# Read_Time_sensor_Tho_AMT.net
KiCad netlist of a schematic drawn in Altium Designer
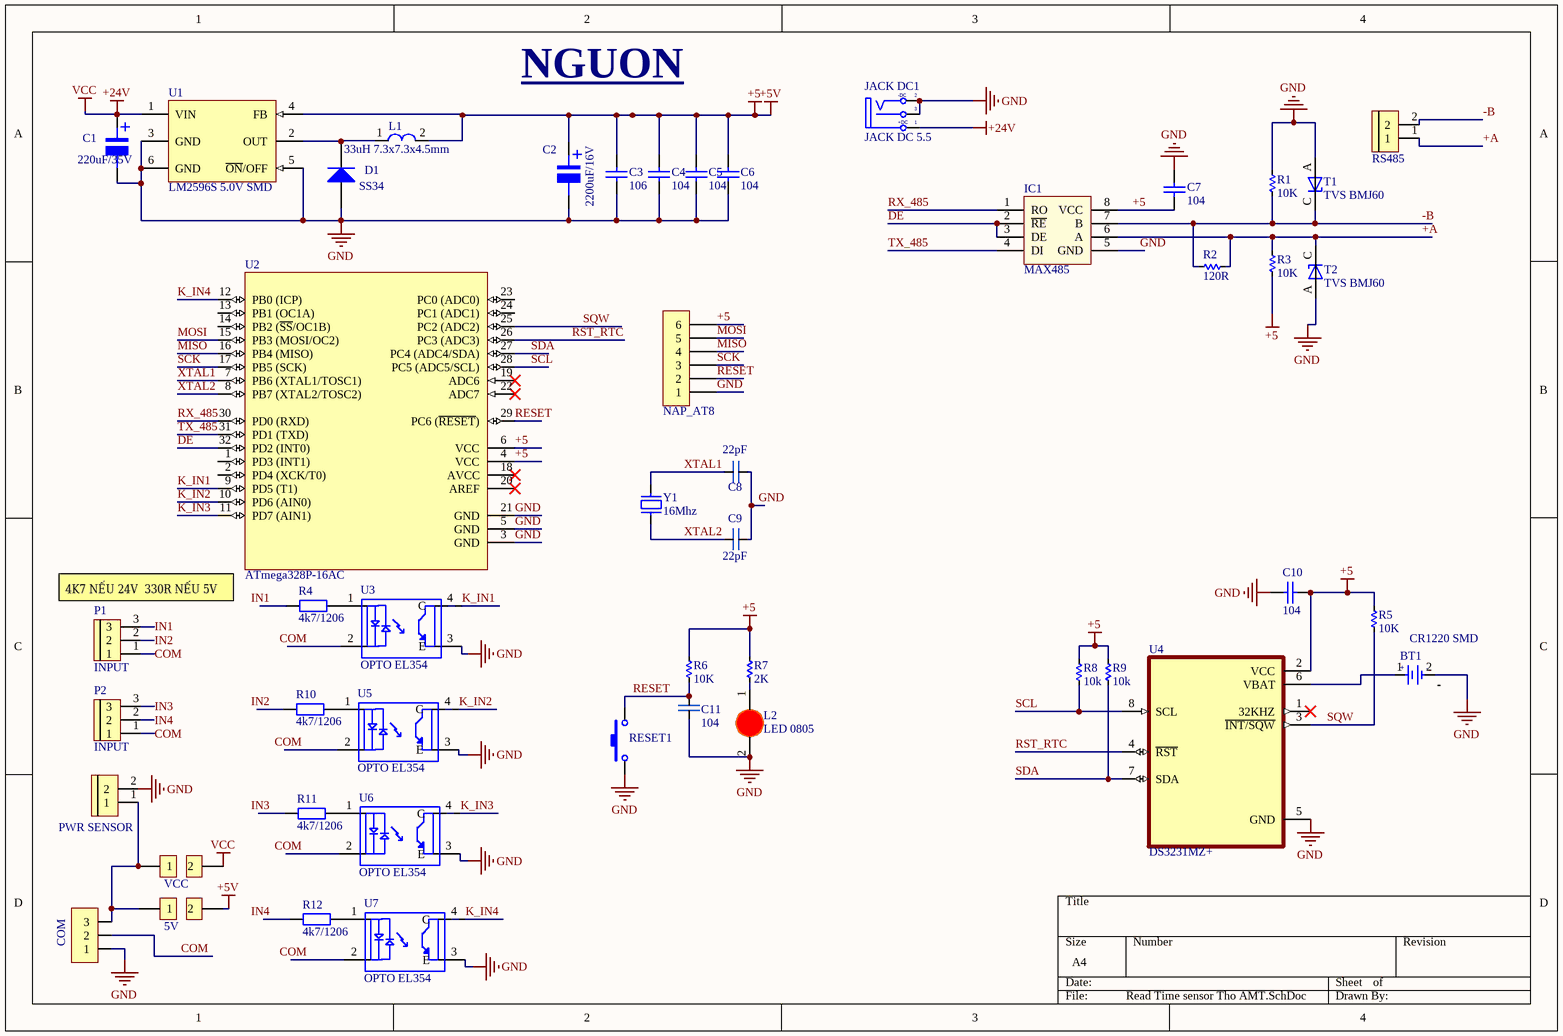
[diagram p0: Read Time sensor Tho AMT.SchDoc]

(export (version "E")
  (design (tool "Eeschema 10.0.6"))
  (components
    (comp (ref "BT1")
      (value "CR1220 SMD")
      (footprint "PIN 2032 DUNG")
      (libsource (lib "NGUYEN VAN ANH HaUI") (part "De pin CR1220 SMD"))
    )
    (comp (ref "C1")
      (value "220uF/35V")
      (footprint "tu nhom 10 (g)")
      (description "Dán 35V")
      (libsource (lib "Altium_Lib_by_KhueNguyenCreator") (part "Tu Nhom 220uF 50V"))
    )
    (comp (ref "C2")
      (value "2200uF/16V")
      (footprint "tu nhom 6.3 (d)")
      (description "Dán")
      (libsource (lib "Altium_Lib_by_KhueNguyenCreator") (part "Tu Nhom 10uF 20V"))
    )
    (comp (ref "C3")
      (value "106")
      (footprint "tu 0805")
      (description "Dán")
      (libsource (lib "Altium_Lib_by_KhueNguyenCreator") (part "Tu 0805 105 50V 10%"))
    )
    (comp (ref "C4")
      (value "104")
      (footprint "tu 0805")
      (description "Dán")
      (libsource (lib "Altium_Lib_by_KhueNguyenCreator") (part "Tu 0805 105 50V 10%"))
    )
    (comp (ref "C5")
      (value "104")
      (footprint "tu 0805")
      (description "Dán")
      (libsource (lib "Altium_Lib_by_KhueNguyenCreator") (part "Tu 0805 105 50V 10%"))
    )
    (comp (ref "C6")
      (value "104")
      (footprint "tu 0805")
      (description "Dán")
      (libsource (lib "Altium_Lib_by_KhueNguyenCreator") (part "Tu 0805 105 50V 10%"))
    )
    (comp (ref "C7")
      (value "104")
      (footprint "TU 0805")
      (description "Dán")
      (libsource (lib "Altium_Lib_by_KhueNguyenCreator") (part "Tu 0805 104 50V 10%"))
    )
    (comp (ref "C8")
      (value "22pF")
      (footprint "TU 0805")
      (libsource (lib "NGUYEN VAN ANH HaUI") (part "TU 0805"))
    )
    (comp (ref "C9")
      (value "22pF")
      (footprint "TU 0805")
      (libsource (lib "NGUYEN VAN ANH HaUI") (part "TU 0805"))
    )
    (comp (ref "C10")
      (value "104")
      (footprint "TU 0805")
      (description "Dán")
      (libsource (lib "Altium_Lib_by_KhueNguyenCreator") (part "Tu 0805 104 50V 10%"))
    )
    (comp (ref "C11")
      (value "104")
      (footprint "TU 0805")
      (libsource (lib "NGUYEN VAN ANH HaUI") (part "TU 0805"))
    )
    (comp (ref "D1")
      (value "SS34")
      (footprint "DIODE SMA")
      (description "Dán")
      (libsource (lib "Altium_Lib_by_KhueNguyenCreator") (part "Diode SS14 ( 1N5819)"))
    )
    (comp (ref "EDG 1")
      (value "RS485")
      (footprint "CON 2 2EDG5.08")
      (description "Cắm")
      (libsource (lib "Altium_Lib_by_KhueNguyenCreator") (part "CON 2 EDG5.08"))
    )
    (comp (ref "EDG 2")
      (value "PWR SENSOR")
      (footprint "CON 2 2EDG5.08")
      (description "Cắm")
      (libsource (lib "Altium_Lib_by_KhueNguyenCreator") (part "CON 2 EDG5.08"))
    )
    (comp (ref "EDG 3")
      (value "COM")
      (footprint "JP 1x3 DT")
      (description "Cắm")
      (libsource (lib "NGUYEN VAN ANH HaUI") (part "JP 1x3 2.54 Duc Thang"))
    )
    (comp (ref "H1")
      (value "NAP_AT8")
      (footprint "Header 6P DC 2.54")
      (description "Cắm")
      (libsource (lib "Altium_Lib_by_KhueNguyenCreator") (part "Header 6P 2.54 Duc Cong"))
    )
    (comp (ref "IC1")
      (value "MAX485")
      (footprint "SO8")
      (description "RS232 - RS485 (Same sn75176)")
      (libsource (lib "Cty1") (part "MAX485"))
    )
    (comp (ref "JACK DC1")
      (value "JACK DC 5.5")
      (footprint "JACK DC 5.5")
      (libsource (lib "NGUYEN VAN ANH HaUI") (part "JACK DC 5.5"))
    )
    (comp (ref "L1")
      (value "33uH 7.3x7.3x4.5mm")
      (footprint "L-SMD-M-7.3x4.5")
      (fields
        (field (name "PARTNO") "78477010")
        (field (name "MANUFACTURER") "Wurth Elektronik")
        (field (name "CREATED BY") "Baojun Chen")
      )
      (libsource (lib "NGUYEN VAN ANH HaUI") (part "L-SMD-1"))
    )
    (comp (ref "L2")
      (value "LED 0805")
      (footprint "LED-0805-Red")
      (description "Dán")
      (libsource (lib "Altium_Lib_by_KhueNguyenCreator") (part "LED 0805 Do"))
    )
    (comp (ref "P1")
      (value "INPUT")
      (footprint "CON 3 3EDG5.08")
      (description "Cắm")
      (libsource (lib "NGUYEN VAN ANH HaUI") (part "CON 3 EDG5.08"))
    )
    (comp (ref "P2")
      (value "INPUT")
      (footprint "CON 3 3EDG5.08")
      (description "Cắm")
      (libsource (lib "NGUYEN VAN ANH HaUI") (part "CON 3 EDG5.08"))
    )
    (comp (ref "P3")
      (value "VCC")
      (footprint "SMT-0805-RES")
      (libsource (lib "NGUYEN VAN ANH HaUI") (part "Pad han noi 2 duong"))
    )
    (comp (ref "P4")
      (value "5V")
      (footprint "SMT-0805-RES")
      (libsource (lib "NGUYEN VAN ANH HaUI") (part "Pad han noi 2 duong"))
    )
    (comp (ref "R1")
      (value "10K")
      (footprint "RES-SMD-0805")
      (description "Resistor")
      (fields
        (field (name "MANUFACTURER") "Generic Components")
        (field (name "PUBLISHER") "Altium Hobart Technology Centre")
      )
      (libsource (lib "NGUYEN VAN ANH HaUI") (part "Res-SMD"))
    )
    (comp (ref "R2")
      (value "120R")
      (footprint "RES-SMD-0805")
      (description "Resistor")
      (fields
        (field (name "MANUFACTURER") "Generic Components")
        (field (name "PUBLISHER") "Altium Hobart Technology Centre")
      )
      (libsource (lib "NGUYEN VAN ANH HaUI") (part "Res-SMD"))
    )
    (comp (ref "R3")
      (value "10K")
      (footprint "RES-SMD-0805")
      (description "Resistor")
      (fields
        (field (name "MANUFACTURER") "Generic Components")
        (field (name "PUBLISHER") "Altium Hobart Technology Centre")
      )
      (libsource (lib "NGUYEN VAN ANH HaUI") (part "Res-SMD"))
    )
    (comp (ref "R4")
      (value "4k7/1206")
      (footprint "tro smd 1206")
      (description "Dán")
      (libsource (lib "NGUYEN VAN ANH HaUI") (part "Tro 0805 5% 10k"))
    )
    (comp (ref "R5")
      (value "10K")
      (footprint "RES-SMD-0805")
      (description "Resistor")
      (fields
        (field (name "MANUFACTURER") "Generic Components")
        (field (name "PUBLISHER") "Altium Hobart Technology Centre")
      )
      (libsource (lib "NGUYEN VAN ANH HaUI") (part "Res-SMD"))
    )
    (comp (ref "R6")
      (value "10K")
      (footprint "RES-SMD-0805")
      (description "Resistor")
      (fields
        (field (name "MANUFACTURER") "Generic Components")
        (field (name "PUBLISHER") "Altium Hobart Technology Centre")
      )
      (libsource (lib "NGUYEN VAN ANH HaUI") (part "Res-SMD"))
    )
    (comp (ref "R7")
      (value "2K")
      (footprint "RES-SMD-0805")
      (description "Resistor")
      (fields
        (field (name "MANUFACTURER") "Generic Components")
        (field (name "PUBLISHER") "Altium Hobart Technology Centre")
      )
      (libsource (lib "NGUYEN VAN ANH HaUI") (part "Res-SMD"))
    )
    (comp (ref "R8")
      (value "10k")
      (footprint "RES-SMD-0805")
      (description "Resistor")
      (fields
        (field (name "MANUFACTURER") "Generic Components")
        (field (name "PUBLISHER") "Altium Hobart Technology Centre")
      )
      (libsource (lib "NGUYEN VAN ANH HaUI") (part "Res-SMD"))
    )
    (comp (ref "R9")
      (value "10k")
      (footprint "RES-SMD-0805")
      (description "Resistor")
      (fields
        (field (name "MANUFACTURER") "Generic Components")
        (field (name "PUBLISHER") "Altium Hobart Technology Centre")
      )
      (libsource (lib "NGUYEN VAN ANH HaUI") (part "Res-SMD"))
    )
    (comp (ref "R10")
      (value "4k7/1206")
      (footprint "tro smd 1206")
      (description "Dán")
      (libsource (lib "NGUYEN VAN ANH HaUI") (part "Tro 0805 5% 10k"))
    )
    (comp (ref "R11")
      (value "4k7/1206")
      (footprint "tro smd 1206")
      (description "Dán")
      (libsource (lib "NGUYEN VAN ANH HaUI") (part "Tro 0805 5% 10k"))
    )
    (comp (ref "R12")
      (value "4k7/1206")
      (footprint "tro smd 1206")
      (description "Dán")
      (libsource (lib "NGUYEN VAN ANH HaUI") (part "Tro 0805 5% 10k"))
    )
    (comp (ref "RESET1")
      (value "Nut Nhan 2 Chan SMD 3x6x2.5")
      (footprint "Nut Nhan 2 Chan SMD 3x6x2.5")
      (libsource (lib "NGUYEN VAN ANH HaUI") (part "Nut Nhan 2 Chan SMD 3x6x2.5"))
    )
    (comp (ref "T1")
      (value "TVS BMJ60")
      (footprint "TVS BMJ60")
      (libsource (lib "NGUYEN VAN ANH HaUI") (part "TVS BMJ60"))
    )
    (comp (ref "T2")
      (value "TVS BMJ60")
      (footprint "TVS BMJ60")
      (libsource (lib "NGUYEN VAN ANH HaUI") (part "TVS BMJ60"))
    )
    (comp (ref "U1")
      (value "LM2596S 5.0V SMD")
      (footprint "TO263-5")
      (description "Dán")
      (libsource (lib "Altium_Lib_by_KhueNguyenCreator") (part "LM2576HVS 5.0V SMD"))
    )
    (comp (ref "U2")
      (value "ATmega328P-16AC")
      (footprint "32A_N")
      (description "8-Bit AVR Microcontroller with 8K Bytes of In-System Programmable Flash Memory")
      (fields (field (name "PUBLISHER") "Altium Limited"))
      (libsource (lib "Atmel Microcontroller 8-Bit AVR") (part "ATmega8-16AC"))
    )
    (comp (ref "U3")
      (value "OPTO EL354")
      (footprint "OPTO EL354")
      (libsource (lib "NGUYEN VAN ANH HaUI") (part "OPTO EL354"))
    )
    (comp (ref "U4")
      (value "DS3231MZ+")
      (footprint "SOIC-8")
      (fields (field (name "MF") "Analog Devices"))
      (libsource (lib "VIN_HW") (part "DS3231MZ+"))
    )
    (comp (ref "U5")
      (value "OPTO EL354")
      (footprint "OPTO EL354")
      (libsource (lib "NGUYEN VAN ANH HaUI") (part "OPTO EL354"))
    )
    (comp (ref "U6")
      (value "OPTO EL354")
      (footprint "OPTO EL354")
      (libsource (lib "NGUYEN VAN ANH HaUI") (part "OPTO EL354"))
    )
    (comp (ref "U7")
      (value "OPTO EL354")
      (footprint "OPTO EL354")
      (libsource (lib "NGUYEN VAN ANH HaUI") (part "OPTO EL354"))
    )
    (comp (ref "Y1")
      (value "16Mhz")
      (footprint "Thach Anh 2 chan SMD5032")
      (description "Crystal For all Crystal 2pin.")
      (libsource (lib "NGUYEN VAN ANH HaUI") (part "Thach Anh 2 chan SMD 5032"))
    )
  )
  (nets
    (net (code "1") (name "+5") (class "Default")
      (node (ref "C10") (pin "1") (pinfunction "1_1") (pintype "passive"))
      (node (ref "C2") (pin "1") (pinfunction "1_1") (pintype "passive"))
      (node (ref "C3") (pin "2") (pinfunction "2_2") (pintype "passive"))
      (node (ref "C4") (pin "2") (pinfunction "2_2") (pintype "passive"))
      (node (ref "C5") (pin "2") (pinfunction "2_2") (pintype "passive"))
      (node (ref "C6") (pin "2") (pinfunction "2_2") (pintype "passive"))
      (node (ref "C7") (pin "1") (pinfunction "1_1") (pintype "passive"))
      (node (ref "H1") (pin "6") (pinfunction "6_6") (pintype "passive"))
      (node (ref "IC1") (pin "8") (pinfunction "VCC_8") (pintype "passive"))
      (node (ref "L1") (pin "2") (pinfunction "2_2") (pintype "passive"))
      (node (ref "P4") (pin "2") (pinfunction "2_2") (pintype "passive"))
      (node (ref "R3") (pin "1") (pinfunction "1_1") (pintype "passive"))
      (node (ref "R5") (pin "1") (pinfunction "1_1") (pintype "passive"))
      (node (ref "R6") (pin "2") (pinfunction "2_2") (pintype "passive"))
      (node (ref "R7") (pin "1") (pinfunction "1_1") (pintype "passive"))
      (node (ref "R8") (pin "1") (pinfunction "1_1") (pintype "passive"))
      (node (ref "R9") (pin "1") (pinfunction "1_1") (pintype "passive"))
      (node (ref "U1") (pin "4") (pinfunction "FB_4") (pintype "input"))
      (node (ref "U2") (pin "4") (pinfunction "VCC_4") (pintype "power_in"))
      (node (ref "U2") (pin "6") (pinfunction "VCC_6") (pintype "power_in"))
      (node (ref "U4") (pin "2") (pinfunction "VCC_2") (pintype "power_in"))
    )
    (net (code "2") (name "+24V") (class "Default")
      (node (ref "C1") (pin "1") (pinfunction "1_1") (pintype "passive"))
      (node (ref "JACK DC1") (pin "1") (pinfunction "T_1") (pintype "passive"))
      (node (ref "P3") (pin "2") (pinfunction "2_2") (pintype "passive"))
      (node (ref "U1") (pin "1") (pinfunction "VIN_1") (pintype "power_in"))
    )
    (net (code "3") (name "/+A") (class "Default")
      (node (ref "EDG 1") (pin "1") (pinfunction "1_1") (pintype "passive"))
      (node (ref "IC1") (pin "6") (pinfunction "A_6") (pintype "passive"))
      (node (ref "R2") (pin "2") (pinfunction "2_2") (pintype "passive"))
      (node (ref "R3") (pin "2") (pinfunction "2_2") (pintype "passive"))
      (node (ref "T2") (pin "C") (pinfunction "C_C") (pintype "passive"))
    )
    (net (code "4") (name "/-B") (class "Default")
      (node (ref "EDG 1") (pin "2") (pinfunction "2_2") (pintype "passive"))
      (node (ref "IC1") (pin "7") (pinfunction "B_7") (pintype "passive"))
      (node (ref "R1") (pin "1") (pinfunction "1_1") (pintype "passive"))
      (node (ref "R2") (pin "1") (pinfunction "1_1") (pintype "passive"))
      (node (ref "T1") (pin "C") (pinfunction "C_C") (pintype "passive"))
    )
    (net (code "5") (name "/COM") (class "Default")
      (node (ref "EDG 3") (pin "2") (pinfunction "2_2") (pintype "passive"))
      (node (ref "P1") (pin "1") (pinfunction "1_1") (pintype "passive"))
      (node (ref "P2") (pin "1") (pinfunction "1_1") (pintype "passive"))
      (node (ref "U3") (pin "2") (pinfunction "C_2") (pintype "passive"))
      (node (ref "U5") (pin "2") (pinfunction "C_2") (pintype "passive"))
      (node (ref "U6") (pin "2") (pinfunction "C_2") (pintype "passive"))
      (node (ref "U7") (pin "2") (pinfunction "C_2") (pintype "passive"))
    )
    (net (code "6") (name "/DE") (class "Default")
      (node (ref "IC1") (pin "2") (pinfunction "~{RE}_2") (pintype "passive"))
      (node (ref "IC1") (pin "3") (pinfunction "DE_3") (pintype "passive"))
      (node (ref "U2") (pin "32") (pinfunction "PD2_(INT0)_32") (pintype "bidirectional"))
    )
    (net (code "7") (name "/IN1") (class "Default")
      (node (ref "P1") (pin "3") (pinfunction "3_3") (pintype "passive"))
      (node (ref "R4") (pin "1") (pinfunction "1_1") (pintype "passive"))
    )
    (net (code "8") (name "/IN2") (class "Default")
      (node (ref "P1") (pin "2") (pinfunction "2_2") (pintype "passive"))
      (node (ref "R10") (pin "1") (pinfunction "1_1") (pintype "passive"))
    )
    (net (code "9") (name "/IN3") (class "Default")
      (node (ref "P2") (pin "3") (pinfunction "3_3") (pintype "passive"))
      (node (ref "R11") (pin "1") (pinfunction "1_1") (pintype "passive"))
    )
    (net (code "10") (name "/IN4") (class "Default")
      (node (ref "P2") (pin "2") (pinfunction "2_2") (pintype "passive"))
      (node (ref "R12") (pin "1") (pinfunction "1_1") (pintype "passive"))
    )
    (net (code "11") (name "/K_IN1") (class "Default")
      (node (ref "U2") (pin "9") (pinfunction "PD5_(T1)_9") (pintype "bidirectional"))
      (node (ref "U3") (pin "4") (pinfunction "C_4") (pintype "passive"))
    )
    (net (code "12") (name "/K_IN2") (class "Default")
      (node (ref "U2") (pin "10") (pinfunction "PD6_(AIN0)_10") (pintype "bidirectional"))
      (node (ref "U5") (pin "4") (pinfunction "C_4") (pintype "passive"))
    )
    (net (code "13") (name "/K_IN3") (class "Default")
      (node (ref "U2") (pin "11") (pinfunction "PD7_(AIN1)_11") (pintype "bidirectional"))
      (node (ref "U6") (pin "4") (pinfunction "C_4") (pintype "passive"))
    )
    (net (code "14") (name "/K_IN4") (class "Default")
      (node (ref "U2") (pin "12") (pinfunction "PB0_(ICP)_12") (pintype "bidirectional"))
      (node (ref "U7") (pin "4") (pinfunction "C_4") (pintype "passive"))
    )
    (net (code "15") (name "/MISO") (class "Default")
      (node (ref "H1") (pin "4") (pinfunction "4_4") (pintype "passive"))
      (node (ref "U2") (pin "16") (pinfunction "PB4_(MISO)_16") (pintype "bidirectional"))
    )
    (net (code "16") (name "/MOSI") (class "Default")
      (node (ref "H1") (pin "5") (pinfunction "5_5") (pintype "passive"))
      (node (ref "U2") (pin "15") (pinfunction "PB3_(MOSI/OC2)_15") (pintype "bidirectional"))
    )
    (net (code "17") (name "/RESET") (class "Default")
      (node (ref "C11") (pin "1") (pinfunction "33_1") (pintype "passive"))
      (node (ref "H1") (pin "2") (pinfunction "2_2") (pintype "passive"))
      (node (ref "R6") (pin "1") (pinfunction "1_1") (pintype "passive"))
      (node (ref "RESET1") (pin "2") (pinfunction "2_2") (pintype "passive"))
      (node (ref "U2") (pin "29") (pinfunction "PC6_(~{RESET})_29") (pintype "bidirectional"))
    )
    (net (code "18") (name "/RST_RTC") (class "Default")
      (node (ref "U2") (pin "26") (pinfunction "PC3_(ADC3)_26") (pintype "bidirectional"))
      (node (ref "U4") (pin "4") (pinfunction "~{RST}_4") (pintype "bidirectional"))
    )
    (net (code "19") (name "/RX_485") (class "Default")
      (node (ref "IC1") (pin "1") (pinfunction "RO_1") (pintype "passive"))
      (node (ref "U2") (pin "30") (pinfunction "PD0_(RXD)_30") (pintype "bidirectional"))
    )
    (net (code "20") (name "/SCK") (class "Default")
      (node (ref "H1") (pin "3") (pinfunction "3_3") (pintype "passive"))
      (node (ref "U2") (pin "17") (pinfunction "PB5_(SCK)_17") (pintype "bidirectional"))
    )
    (net (code "21") (name "/SCL") (class "Default")
      (node (ref "R8") (pin "2") (pinfunction "2_2") (pintype "passive"))
      (node (ref "U2") (pin "28") (pinfunction "PC5_(ADC5/SCL)_28") (pintype "bidirectional"))
      (node (ref "U4") (pin "8") (pinfunction "SCL_8") (pintype "input"))
    )
    (net (code "22") (name "/SDA") (class "Default")
      (node (ref "R9") (pin "2") (pinfunction "2_2") (pintype "passive"))
      (node (ref "U2") (pin "27") (pinfunction "PC4_(ADC4/SDA)_27") (pintype "bidirectional"))
      (node (ref "U4") (pin "7") (pinfunction "SDA_7") (pintype "bidirectional"))
    )
    (net (code "23") (name "/SQW") (class "Default")
      (node (ref "R5") (pin "2") (pinfunction "2_2") (pintype "passive"))
      (node (ref "U2") (pin "25") (pinfunction "PC2_(ADC2)_25") (pintype "bidirectional"))
      (node (ref "U4") (pin "3") (pinfunction "~{INT/SQW}_3") (pintype "output"))
    )
    (net (code "24") (name "/TX_485") (class "Default")
      (node (ref "IC1") (pin "4") (pinfunction "DI_4") (pintype "passive"))
      (node (ref "U2") (pin "31") (pinfunction "PD1_(TXD)_31") (pintype "bidirectional"))
    )
    (net (code "25") (name "/XTAL1") (class "Default")
      (node (ref "C8") (pin "1") (pinfunction "33_1") (pintype "passive"))
      (node (ref "U2") (pin "7") (pinfunction "PB6_(XTAL1/TOSC1)_7") (pintype "bidirectional"))
      (node (ref "Y1") (pin "2") (pinfunction "2_2") (pintype "passive"))
    )
    (net (code "26") (name "/XTAL2") (class "Default")
      (node (ref "C9") (pin "1") (pinfunction "33_1") (pintype "passive"))
      (node (ref "U2") (pin "8") (pinfunction "PB7_(XTAL2/TOSC2)_8") (pintype "bidirectional"))
      (node (ref "Y1") (pin "1") (pinfunction "1_1") (pintype "passive"))
    )
    (net (code "27") (name "GND") (class "Default")
      (node (ref "BT1") (pin "2") (pinfunction "GND_2") (pintype "passive"))
      (node (ref "C1") (pin "2") (pinfunction "2_2") (pintype "passive"))
      (node (ref "C10") (pin "2") (pinfunction "2_2") (pintype "passive"))
      (node (ref "C11") (pin "2") (pinfunction "2_2") (pintype "passive"))
      (node (ref "C2") (pin "2") (pinfunction "2_2") (pintype "passive"))
      (node (ref "C3") (pin "1") (pinfunction "1_1") (pintype "passive"))
      (node (ref "C4") (pin "1") (pinfunction "1_1") (pintype "passive"))
      (node (ref "C5") (pin "1") (pinfunction "1_1") (pintype "passive"))
      (node (ref "C6") (pin "1") (pinfunction "1_1") (pintype "passive"))
      (node (ref "C7") (pin "2") (pinfunction "2_2") (pintype "passive"))
      (node (ref "C8") (pin "2") (pinfunction "2_2") (pintype "passive"))
      (node (ref "C9") (pin "2") (pinfunction "2_2") (pintype "passive"))
      (node (ref "D1") (pin "1") (pinfunction "A_1") (pintype "passive"))
      (node (ref "EDG 2") (pin "2") (pinfunction "2_2") (pintype "passive"))
      (node (ref "EDG 3") (pin "1") (pinfunction "1_1") (pintype "passive"))
      (node (ref "H1") (pin "1") (pinfunction "1_1") (pintype "passive"))
      (node (ref "IC1") (pin "5") (pinfunction "GND_5") (pintype "passive"))
      (node (ref "JACK DC1") (pin "2") (pinfunction "TN_2") (pintype "passive"))
      (node (ref "JACK DC1") (pin "3") (pinfunction "S_3") (pintype "power_in"))
      (node (ref "L2") (pin "2") (pinfunction "K_2") (pintype "passive"))
      (node (ref "R1") (pin "2") (pinfunction "2_2") (pintype "passive"))
      (node (ref "RESET1") (pin "1") (pinfunction "1_1") (pintype "passive"))
      (node (ref "T1") (pin "A") (pinfunction "A_A") (pintype "passive"))
      (node (ref "T2") (pin "A") (pinfunction "A_A") (pintype "passive"))
      (node (ref "U1") (pin "3") (pinfunction "GND_3") (pintype "power_in"))
      (node (ref "U1") (pin "5") (pinfunction "~{ON}/OFF_5") (pintype "input"))
      (node (ref "U1") (pin "6") (pinfunction "GND_6") (pintype "passive"))
      (node (ref "U2") (pin "21") (pinfunction "GND_21") (pintype "power_in"))
      (node (ref "U2") (pin "3") (pinfunction "GND_3") (pintype "power_in"))
      (node (ref "U2") (pin "5") (pinfunction "GND_5") (pintype "power_in"))
      (node (ref "U3") (pin "3") (pinfunction "E_3") (pintype "passive"))
      (node (ref "U4") (pin "5") (pinfunction "GND_5") (pintype "power_in"))
      (node (ref "U5") (pin "3") (pinfunction "E_3") (pintype "passive"))
      (node (ref "U6") (pin "3") (pinfunction "E_3") (pintype "passive"))
      (node (ref "U7") (pin "3") (pinfunction "E_3") (pintype "passive"))
    )
    (net (code "28") (name "Net-(BT1-+3V)") (class "Default")
      (node (ref "BT1") (pin "1") (pinfunction "+3V_1") (pintype "passive"))
      (node (ref "U4") (pin "6") (pinfunction "VBAT_6") (pintype "power_in"))
    )
    (net (code "29") (name "Net-(D1-K)") (class "Default")
      (node (ref "D1") (pin "2") (pinfunction "K_2") (pintype "passive"))
      (node (ref "L1") (pin "1") (pinfunction "1_1") (pintype "passive"))
      (node (ref "U1") (pin "2") (pinfunction "OUT_2") (pintype "power_in"))
    )
    (net (code "30") (name "Net-(EDG 2-Pad1)") (class "Default")
      (node (ref "EDG 2") (pin "1") (pinfunction "1_1") (pintype "passive"))
      (node (ref "EDG 3") (pin "3") (pinfunction "3_3") (pintype "passive"))
      (node (ref "P3") (pin "1") (pinfunction "1_1") (pintype "passive"))
      (node (ref "P4") (pin "1") (pinfunction "1_1") (pintype "passive"))
    )
    (net (code "31") (name "Net-(L2-A)") (class "Default")
      (node (ref "L2") (pin "1") (pinfunction "A_1") (pintype "passive"))
      (node (ref "R7") (pin "2") (pinfunction "2_2") (pintype "passive"))
    )
    (net (code "32") (name "Net-(U3-A)") (class "Default")
      (node (ref "R4") (pin "2") (pinfunction "2_2") (pintype "passive"))
      (node (ref "U3") (pin "1") (pinfunction "A_1") (pintype "passive"))
    )
    (net (code "33") (name "Net-(U5-A)") (class "Default")
      (node (ref "R10") (pin "2") (pinfunction "2_2") (pintype "passive"))
      (node (ref "U5") (pin "1") (pinfunction "A_1") (pintype "passive"))
    )
    (net (code "34") (name "Net-(U6-A)") (class "Default")
      (node (ref "R11") (pin "2") (pinfunction "2_2") (pintype "passive"))
      (node (ref "U6") (pin "1") (pinfunction "A_1") (pintype "passive"))
    )
    (net (code "35") (name "Net-(U7-A)") (class "Default")
      (node (ref "R12") (pin "2") (pinfunction "2_2") (pintype "passive"))
      (node (ref "U7") (pin "1") (pinfunction "A_1") (pintype "passive"))
    )
    (net (code "36") (name "unconnected-(BT1-Pad0)") (class "Default")
      (node (ref "BT1") (pin "0") (pinfunction "0_0") (pintype "passive"))
    )
    (net (code "37") (name "unconnected-(U2-ADC6-Pad19)") (class "Default")
      (node (ref "U2") (pin "19") (pinfunction "ADC6_19") (pintype "input+no_connect"))
    )
    (net (code "38") (name "unconnected-(U2-ADC7-Pad22)") (class "Default")
      (node (ref "U2") (pin "22") (pinfunction "ADC7_22") (pintype "input+no_connect"))
    )
    (net (code "39") (name "unconnected-(U2-AREF-Pad20)") (class "Default")
      (node (ref "U2") (pin "20") (pinfunction "AREF_20") (pintype "passive+no_connect"))
    )
    (net (code "40") (name "unconnected-(U2-AVCC-Pad18)") (class "Default")
      (node (ref "U2") (pin "18") (pinfunction "AVCC_18") (pintype "power_in+no_connect"))
    )
    (net (code "41") (name "unconnected-(U2-PB1_(OC1A)-Pad13)") (class "Default")
      (node (ref "U2") (pin "13") (pinfunction "PB1_(OC1A)_13") (pintype "bidirectional"))
    )
    (net (code "42") (name "unconnected-(U2-PB2_(~{SS}{slash}OC1B)-Pad14)") (class "Default")
      (node (ref "U2") (pin "14") (pinfunction "PB2_(~{SS}/OC1B)_14") (pintype "bidirectional"))
    )
    (net (code "43") (name "unconnected-(U2-PC0_(ADC0)-Pad23)") (class "Default")
      (node (ref "U2") (pin "23") (pinfunction "PC0_(ADC0)_23") (pintype "bidirectional"))
    )
    (net (code "44") (name "unconnected-(U2-PC1_(ADC1)-Pad24)") (class "Default")
      (node (ref "U2") (pin "24") (pinfunction "PC1_(ADC1)_24") (pintype "bidirectional"))
    )
    (net (code "45") (name "unconnected-(U2-PD3_(INT1)-Pad1)") (class "Default")
      (node (ref "U2") (pin "1") (pinfunction "PD3_(INT1)_1") (pintype "bidirectional"))
    )
    (net (code "46") (name "unconnected-(U2-PD4_(XCK{slash}T0)-Pad2)") (class "Default")
      (node (ref "U2") (pin "2") (pinfunction "PD4_(XCK/T0)_2") (pintype "bidirectional"))
    )
    (net (code "47") (name "unconnected-(U4-32KHZ-Pad1)") (class "Default")
      (node (ref "U4") (pin "1") (pinfunction "32KHZ_1") (pintype "output+no_connect"))
    )
  )
)
